# 1-Top.net
KiCad netlist of a schematic drawn in Altium Designer
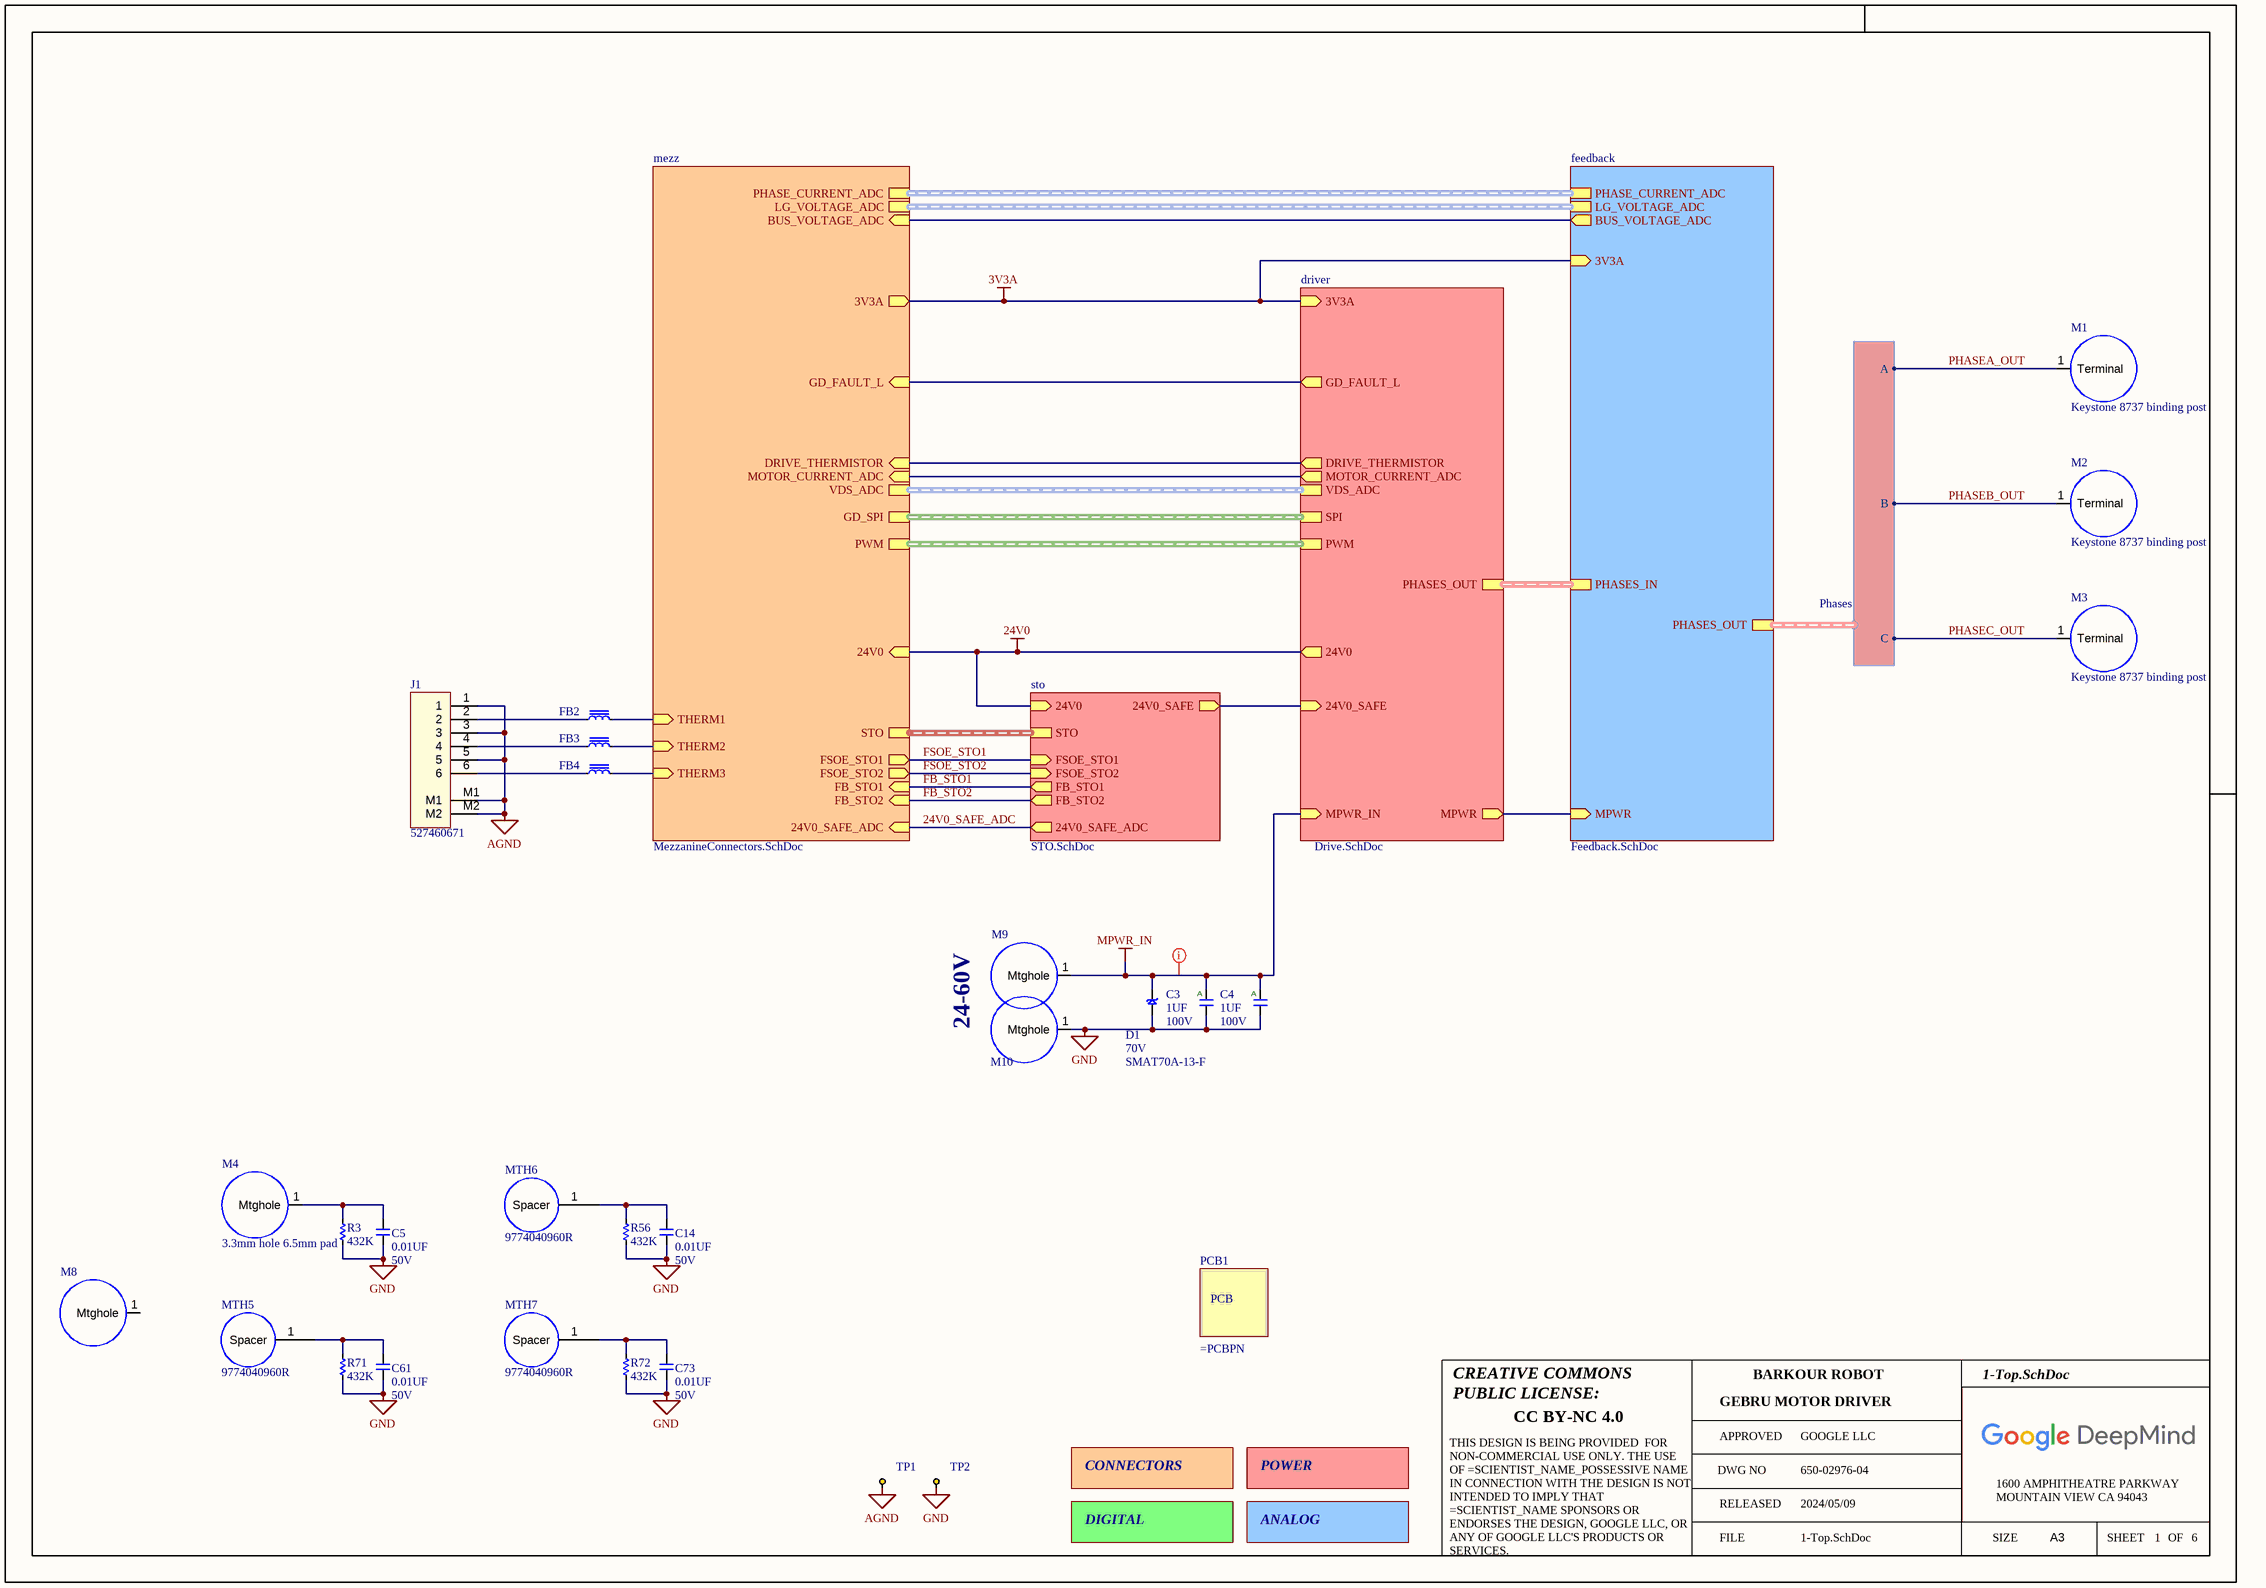
[diagram p0: 1-Top.SchDoc]

(export (version "E")
  (design (tool "Eeschema 10.0.6"))
  (components
    (comp (ref "C3")
      (value "1UF")
      (footprint "C0805")
      (description "CAP, CER, X7S, 1uF, 20%, 100V, 0805")
      (fields (field (name "MFG") "TDK") (field (name "VOLTAGE") "100V") (field (name "TOLERANCE") "20%"))
      (libsource (lib "AltiumReleaseLibDB") (part "__Template_Cap_Auto"))
    )
    (comp (ref "C4")
      (value "1UF")
      (footprint "C0805")
      (description "CAP, CER, X7S, 1uF, 20%, 100V, 0805")
      (fields (field (name "MFG") "TDK") (field (name "VOLTAGE") "100V") (field (name "TOLERANCE") "20%"))
      (libsource (lib "AltiumReleaseLibDB") (part "__Template_Cap_Auto"))
    )
    (comp (ref "C5")
      (value "0.01UF")
      (footprint "C0402")
      (description "CAP, CER, X7R, 0.01uF, 50V, 20%, 0402, 0.56mm T")
      (fields (field (name "MFG") "KEMET") (field (name "VOLTAGE") "50V") (field (name "TOLERANCE") "20%"))
      (libsource (lib "AltiumReleaseLibDB") (part "__Template_Cap"))
    )
    (comp (ref "C14")
      (value "0.01UF")
      (footprint "C0402")
      (description "CAP, CER, X7R, 0.01uF, 50V, 20%, 0402, 0.56mm T")
      (fields (field (name "MFG") "KEMET") (field (name "VOLTAGE") "50V") (field (name "TOLERANCE") "20%"))
      (libsource (lib "AltiumReleaseLibDB") (part "__Template_Cap"))
    )
    (comp (ref "C61")
      (value "0.01UF")
      (footprint "C0402")
      (description "CAP, CER, X7R, 0.01uF, 50V, 20%, 0402, 0.56mm T")
      (fields (field (name "MFG") "KEMET") (field (name "VOLTAGE") "50V") (field (name "TOLERANCE") "20%"))
      (libsource (lib "AltiumReleaseLibDB") (part "__Template_Cap"))
    )
    (comp (ref "C73")
      (value "0.01UF")
      (footprint "C0402")
      (description "CAP, CER, X7R, 0.01uF, 50V, 20%, 0402, 0.56mm T")
      (fields (field (name "MFG") "KEMET") (field (name "VOLTAGE") "50V") (field (name "TOLERANCE") "20%"))
      (libsource (lib "AltiumReleaseLibDB") (part "__Template_Cap"))
    )
    (comp (ref "D1")
      (value "SMAT70A-13-F")
      (footprint "SMA_B130-13-F")
      (description "DIODE, TVS, UNI-DIR, 70VR, 100VCL, 400W, 140PF @1MHZ, SMA")
      (fields
        (field (name "MFG") "Diodes Incorporated")
        (field (name "VOLTAGE - DC REVERSE (VR) (MAX)") "70V")
        (field (name "Comment") "__Template_Diode_TVS_A/K")
      )
      (libsource (lib "AltiumReleaseLibDB") (part "__Template_Diode_TVS_A/K"))
    )
    (comp (ref "FB2")
      (value "LAIRD MI0603L221R-10")
      (footprint "INDC160X80X105L30N")
      (description "FERRITE BEAD 220 OHM 0603 1LN")
      (fields
        (field (name "MANUFACTURER") "Laird Technologies")
        (field (name "MANUFACTURER PART NUMBER") "MI0603L221R-10")
      )
      (libsource (lib "Components") (part "FB"))
    )
    (comp (ref "FB3")
      (value "LAIRD MI0603L221R-10")
      (footprint "INDC160X80X105L30N")
      (description "FERRITE BEAD 220 OHM 0603 1LN")
      (fields
        (field (name "MANUFACTURER") "Laird Technologies")
        (field (name "MANUFACTURER PART NUMBER") "MI0603L221R-10")
      )
      (libsource (lib "Components") (part "FB"))
    )
    (comp (ref "FB4")
      (value "LAIRD MI0603L221R-10")
      (footprint "INDC160X80X105L30N")
      (description "FERRITE BEAD 220 OHM 0603 1LN")
      (fields
        (field (name "MANUFACTURER") "Laird Technologies")
        (field (name "MANUFACTURER PART NUMBER") "MI0603L221R-10")
      )
      (libsource (lib "Components") (part "FB"))
    )
    (comp (ref "J1")
      (value "~")
      (footprint "MOLEX_FPC_527460671")
      (description "CONN, FFC, RA, 1x6 P, 0.5MM PITCH, 2.3MM H, GOLD, SMD")
      (fields (field (name "MFG") "Molex") (field (name "MFG P/N") "527460671"))
      (libsource (lib "AltiumReleaseLibDB") (part "__Template_Connector_1X6_2M"))
    )
    (comp (ref "M1")
      (value "Keystone 8737 binding post")
      (footprint "Keystone_8737")
      (description "1.5mm hole 5.6mm pad")
      (libsource (lib "MiscSch1") (part "Keystone_8737_post"))
    )
    (comp (ref "M2")
      (value "Keystone 8737 binding post")
      (footprint "Keystone_8737")
      (description "1.5mm hole 5.6mm pad")
      (libsource (lib "MiscSch1") (part "Keystone_8737_post"))
    )
    (comp (ref "M3")
      (value "Keystone 8737 binding post")
      (footprint "Keystone_8737")
      (description "1.5mm hole 5.6mm pad")
      (libsource (lib "MiscSch1") (part "Keystone_8737_post"))
    )
    (comp (ref "M4")
      (value "3.3mm hole 6.5mm pad")
      (footprint "3.3HOLE6.5PAD")
      (libsource (lib "MiscSch1") (part "MtgHole_2"))
    )
    (comp (ref "M8")
      (value "3.7mm hole 5mm pad")
      (footprint "3.7hole5pad")
      (libsource (lib "MiscSch1") (part "MtgHole"))
    )
    (comp (ref "M9")
      (value "1.3mm hole 5mm pad")
      (footprint "1.7hole5padSQ")
      (libsource (lib "MiscSch1") (part "MtgHole_1"))
    )
    (comp (ref "M10")
      (value "1.3mm hole 5mm pad")
      (footprint "1.7hole5padRD")
      (libsource (lib "MiscSch1") (part "MtgHole_1"))
    )
    (comp (ref "MTH5")
      (value "9774040960R")
      (footprint "9774040960R")
      (description "Spacer Material: Steel Mounting: SMT Series: WA-SMST For ø: 3.3 mm")
      (fields (field (name "MANUFACTURER") "Wurth Electronics"))
      (libsource (lib "MiscSch1") (part "Wurth_4mm_Spacer_9774040960R"))
    )
    (comp (ref "MTH6")
      (value "9774040960R")
      (footprint "9774040960R")
      (description "Spacer Material: Steel Mounting: SMT Series: WA-SMST For ø: 3.3 mm")
      (fields (field (name "MANUFACTURER") "Wurth Electronics"))
      (libsource (lib "MiscSch1") (part "Wurth_4mm_Spacer_9774040960R"))
    )
    (comp (ref "MTH7")
      (value "9774040960R")
      (footprint "9774040960R")
      (description "Spacer Material: Steel Mounting: SMT Series: WA-SMST For ø: 3.3 mm")
      (fields (field (name "MANUFACTURER") "Wurth Electronics"))
      (libsource (lib "MiscSch1") (part "Wurth_4mm_Spacer_9774040960R"))
    )
    (comp (ref "PCB1") (value "~") (description "PCB") (libsource (lib "AltiumReleaseLibDB") (part "Label")))
    (comp (ref "R3")
      (value "432K")
      (footprint "R0805")
      (description "Resistor, 432K Ohms, 0805, 0.125W, ±1%")
      (fields (field (name "MFG") "YAGEO") (field (name "POWER") "1/8W"))
      (libsource (lib "AltiumReleaseLibDB") (part "__Template_Resistor"))
    )
    (comp (ref "R56")
      (value "432K")
      (footprint "R0805")
      (description "Resistor, 432K Ohms, 0805, 0.125W, ±1%")
      (fields (field (name "MFG") "YAGEO") (field (name "POWER") "1/8W"))
      (libsource (lib "AltiumReleaseLibDB") (part "__Template_Resistor"))
    )
    (comp (ref "R71")
      (value "432K")
      (footprint "R0805")
      (description "Resistor, 432K Ohms, 0805, 0.125W, ±1%")
      (fields (field (name "MFG") "YAGEO") (field (name "POWER") "1/8W"))
      (libsource (lib "AltiumReleaseLibDB") (part "__Template_Resistor"))
    )
    (comp (ref "R72")
      (value "432K")
      (footprint "R0805")
      (description "Resistor, 432K Ohms, 0805, 0.125W, ±1%")
      (fields (field (name "MFG") "YAGEO") (field (name "POWER") "1/8W"))
      (libsource (lib "AltiumReleaseLibDB") (part "__Template_Resistor"))
    )
    (comp (ref "TP1")
      (value "TEST_KEYSTONE5001")
      (footprint "TP_KEYSTONE_5001")
      (description "PC TEST POINT TH RING")
      (fields
        (field (name "MANUFACTURER") "Keystone Electronics")
        (field (name "MANUFACTURER PART NUMBER") "5001")
      )
      (libsource (lib "miscellaneous") (part "TEST_KEYSTONE5001"))
    )
    (comp (ref "TP2")
      (value "TEST_KEYSTONE5001")
      (footprint "TP_KEYSTONE_5001")
      (description "PC TEST POINT TH RING")
      (fields
        (field (name "MANUFACTURER") "Keystone Electronics")
        (field (name "MANUFACTURER PART NUMBER") "5001")
      )
      (libsource (lib "miscellaneous") (part "TEST_KEYSTONE5001"))
    )
  )
  (nets
    (net (code "15") (name "/PHASEA_OUT") (class "Default")
      (node (ref "M1") (pin "1") (pinfunction "Terminal_1") (pintype "passive"))
    )
    (net (code "16") (name "/PHASEB_OUT") (class "Default")
      (node (ref "M2") (pin "1") (pinfunction "Terminal_1") (pintype "passive"))
    )
    (net (code "17") (name "/PHASEC_OUT") (class "Default")
      (node (ref "M3") (pin "1") (pinfunction "Terminal_1") (pintype "passive"))
    )
    (net (code "22") (name "/THERM1") (class "Default") (node (ref "FB2") (pin "2") (pintype "passive")))
    (net (code "23") (name "/THERM2") (class "Default") (node (ref "FB3") (pin "2") (pintype "passive")))
    (net (code "24") (name "/THERM3") (class "Default") (node (ref "FB4") (pin "2") (pintype "passive")))
    (net (code "29") (name "AGND") (class "Default")
      (node (ref "J1") (pin "1") (pinfunction "1_1") (pintype "passive"))
      (node (ref "J1") (pin "3") (pinfunction "3_3") (pintype "passive"))
      (node (ref "J1") (pin "5") (pinfunction "5_5") (pintype "passive"))
      (node (ref "J1") (pin "M1") (pinfunction "M1_M1") (pintype "passive"))
      (node (ref "J1") (pin "M2") (pinfunction "M2_M2") (pintype "passive"))
      (node (ref "TP1") (pin "1") (pintype "passive"))
    )
    (net (code "30") (name "GND") (class "Default")
      (node (ref "C14") (pin "2") (pintype "passive"))
      (node (ref "C3") (pin "2") (pintype "passive"))
      (node (ref "C4") (pin "2") (pintype "passive"))
      (node (ref "C5") (pin "2") (pintype "passive"))
      (node (ref "C61") (pin "2") (pintype "passive"))
      (node (ref "C73") (pin "2") (pintype "passive"))
      (node (ref "D1") (pin "A") (pinfunction "A_A") (pintype "passive"))
      (node (ref "M10") (pin "1") (pinfunction "Mtghole_1") (pintype "passive"))
      (node (ref "R3") (pin "1") (pintype "passive"))
      (node (ref "R56") (pin "1") (pintype "passive"))
      (node (ref "R71") (pin "1") (pintype "passive"))
      (node (ref "R72") (pin "1") (pintype "passive"))
      (node (ref "TP2") (pin "1") (pintype "passive"))
    )
    (net (code "31") (name "MPWR_IN") (class "Default")
      (node (ref "C3") (pin "1") (pintype "passive"))
      (node (ref "C4") (pin "1") (pintype "passive"))
      (node (ref "D1") (pin "K") (pinfunction "K_K") (pintype "passive"))
      (node (ref "M9") (pin "1") (pinfunction "Mtghole_1") (pintype "passive"))
    )
    (net (code "32") (name "Net-(FB2-Pad1)") (class "Default")
      (node (ref "FB2") (pin "1") (pintype "passive"))
      (node (ref "J1") (pin "2") (pinfunction "2_2") (pintype "passive"))
    )
    (net (code "33") (name "Net-(FB3-Pad1)") (class "Default")
      (node (ref "FB3") (pin "1") (pintype "passive"))
      (node (ref "J1") (pin "4") (pinfunction "4_4") (pintype "passive"))
    )
    (net (code "34") (name "Net-(FB4-Pad1)") (class "Default")
      (node (ref "FB4") (pin "1") (pintype "passive"))
      (node (ref "J1") (pin "6") (pinfunction "6_6") (pintype "passive"))
    )
    (net (code "35") (name "Net-(M4-Mtghole)") (class "Default")
      (node (ref "C5") (pin "1") (pintype "passive"))
      (node (ref "M4") (pin "1") (pinfunction "Mtghole_1") (pintype "passive"))
      (node (ref "R3") (pin "2") (pintype "passive"))
    )
    (net (code "36") (name "Net-(MTH5-Spacer)") (class "Default")
      (node (ref "C61") (pin "1") (pintype "passive"))
      (node (ref "MTH5") (pin "1") (pinfunction "Spacer_1") (pintype "passive"))
      (node (ref "R71") (pin "2") (pintype "passive"))
    )
    (net (code "37") (name "Net-(MTH6-Spacer)") (class "Default")
      (node (ref "C14") (pin "1") (pintype "passive"))
      (node (ref "MTH6") (pin "1") (pinfunction "Spacer_1") (pintype "passive"))
      (node (ref "R56") (pin "2") (pintype "passive"))
    )
    (net (code "38") (name "Net-(MTH7-Spacer)") (class "Default")
      (node (ref "C73") (pin "1") (pintype "passive"))
      (node (ref "MTH7") (pin "1") (pinfunction "Spacer_1") (pintype "passive"))
      (node (ref "R72") (pin "2") (pintype "passive"))
    )
    (net (code "39") (name "unconnected-(M8-Mtghole-Pad1)") (class "Default")
      (node (ref "M8") (pin "1") (pinfunction "Mtghole_1") (pintype "passive"))
    )
  )
)
